# LPDDR4X_SDRAM.net
KiCad netlist of a schematic drawn in Altium Designer
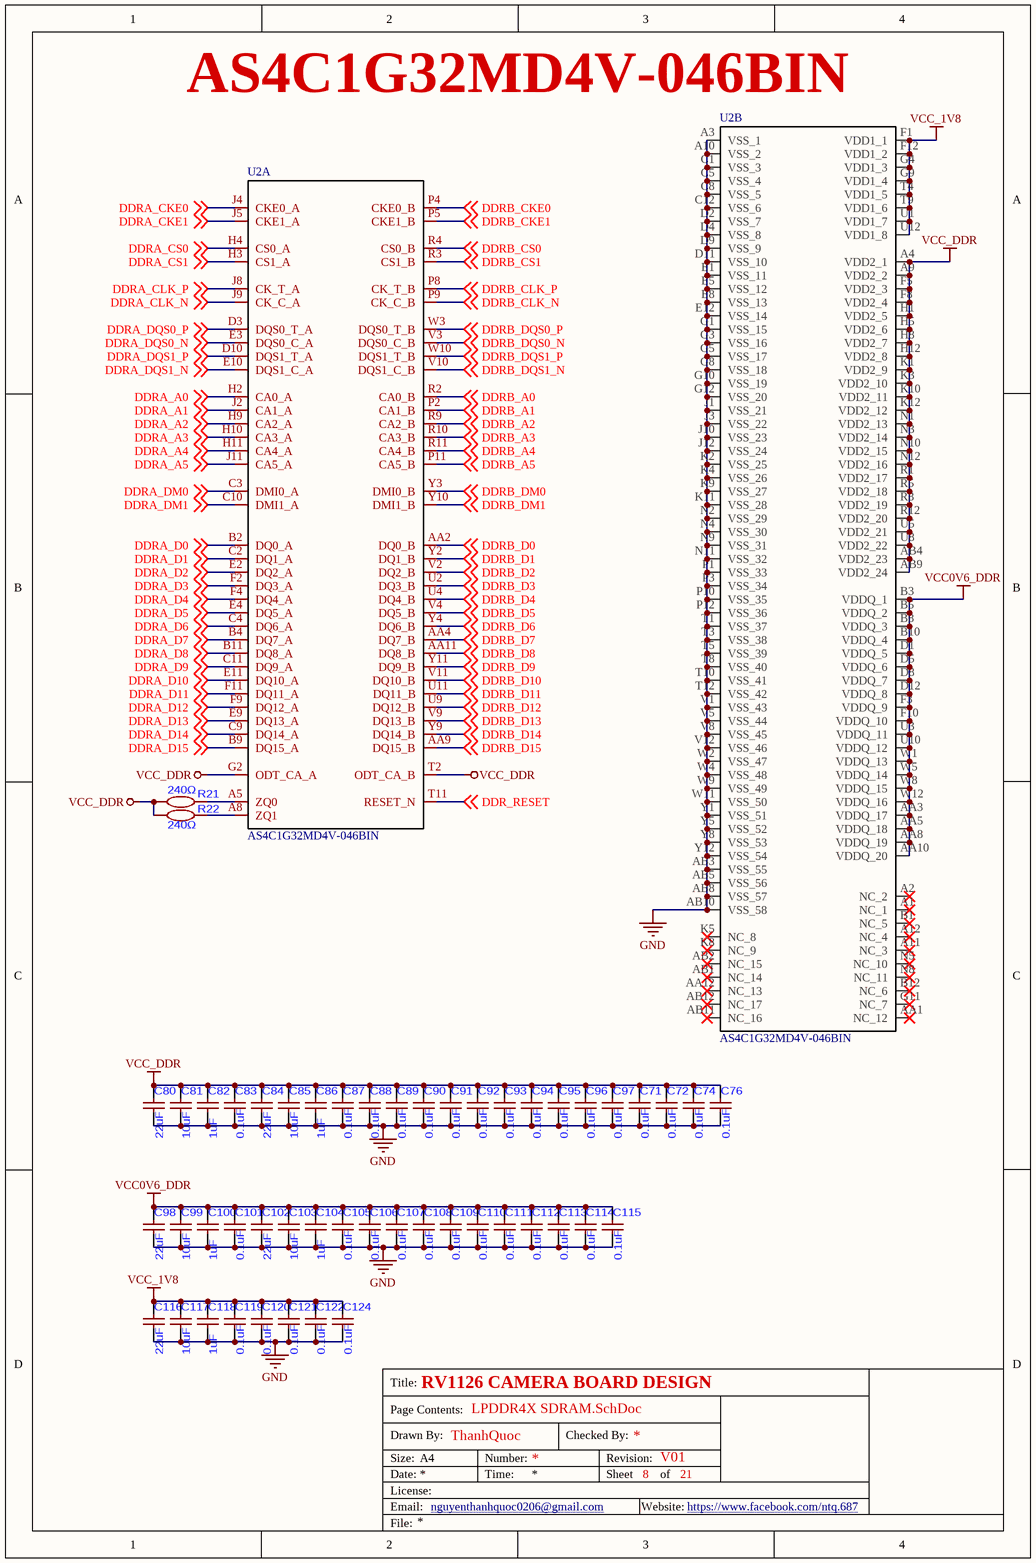
[diagram p0: LPDDR4X SDRAM.SchDoc]

(export (version "E")
  (design (tool "Eeschema 10.0.6"))
  (components
    (comp (ref "C71")
      (value "0.1uF")
      (footprint "C0201")
      (description "0.1uF ±10% 6.3V Ceramic Capacitor X5R 0201")
      (libsource (lib "Schlib1") (part "CAP_100nF-6.3V-10%-0201_1"))
    )
    (comp (ref "C72")
      (value "0.1uF")
      (footprint "C0201")
      (description "0.1uF ±10% 6.3V Ceramic Capacitor X5R 0201")
      (libsource (lib "Schlib1") (part "CAP_100nF-6.3V-10%-0201_1"))
    )
    (comp (ref "C74")
      (value "0.1uF")
      (footprint "C0201")
      (description "0.1uF ±10% 6.3V Ceramic Capacitor X5R 0201")
      (libsource (lib "Schlib1") (part "CAP_100nF-6.3V-10%-0201_1"))
    )
    (comp (ref "C76")
      (value "0.1uF")
      (footprint "C0201")
      (description "0.1uF ±10% 6.3V Ceramic Capacitor X5R 0201")
      (libsource (lib "Schlib1") (part "CAP_100nF-6.3V-10%-0201_1"))
    )
    (comp (ref "C80")
      (value "22uF")
      (footprint "C0402")
      (description "22uF X5R ±20% 6.3V 0402 Ceramic Capacitors RoHS")
      (libsource (lib "Schlib1") (part "CAP_22uF-6.3V-20%-0402"))
    )
    (comp (ref "C81")
      (value "10uF")
      (footprint "C0402")
      (description "10µF ±20% 10V Ceramic Capacitor X5R 0402 (1005 Metric)")
      (libsource (lib "Schlib1") (part "CAP_10uF-10V-20%-0402"))
    )
    (comp (ref "C82")
      (value "1uF")
      (footprint "C0201")
      (description "1uF ±10% 6.3V Ceramic Capacitor X5R 0201")
      (libsource (lib "Schlib1") (part "CAP_1uF-6.3V-10%-0201"))
    )
    (comp (ref "C83")
      (value "0.1uF")
      (footprint "C0201")
      (description "0.1uF ±10% 6.3V Ceramic Capacitor X5R 0201")
      (libsource (lib "Schlib1") (part "CAP_100nF-6.3V-10%-0201_1"))
    )
    (comp (ref "C84")
      (value "22uF")
      (footprint "C0402")
      (description "22uF X5R ±20% 6.3V 0402 Ceramic Capacitors RoHS")
      (libsource (lib "Schlib1") (part "CAP_22uF-6.3V-20%-0402"))
    )
    (comp (ref "C85")
      (value "10uF")
      (footprint "C0402")
      (description "10µF ±20% 10V Ceramic Capacitor X5R 0402 (1005 Metric)")
      (libsource (lib "Schlib1") (part "CAP_10uF-10V-20%-0402"))
    )
    (comp (ref "C86")
      (value "1uF")
      (footprint "C0201")
      (description "1uF ±10% 6.3V Ceramic Capacitor X5R 0201")
      (libsource (lib "Schlib1") (part "CAP_1uF-6.3V-10%-0201"))
    )
    (comp (ref "C87")
      (value "0.1uF")
      (footprint "C0201")
      (description "0.1uF ±10% 6.3V Ceramic Capacitor X5R 0201")
      (libsource (lib "Schlib1") (part "CAP_100nF-6.3V-10%-0201_1"))
    )
    (comp (ref "C88")
      (value "0.1uF")
      (footprint "C0201")
      (description "0.1uF ±10% 6.3V Ceramic Capacitor X5R 0201")
      (libsource (lib "Schlib1") (part "CAP_100nF-6.3V-10%-0201_1"))
    )
    (comp (ref "C89")
      (value "0.1uF")
      (footprint "C0201")
      (description "0.1uF ±10% 6.3V Ceramic Capacitor X5R 0201")
      (libsource (lib "Schlib1") (part "CAP_100nF-6.3V-10%-0201_1"))
    )
    (comp (ref "C90")
      (value "0.1uF")
      (footprint "C0201")
      (description "0.1uF ±10% 6.3V Ceramic Capacitor X5R 0201")
      (libsource (lib "Schlib1") (part "CAP_100nF-6.3V-10%-0201_1"))
    )
    (comp (ref "C91")
      (value "0.1uF")
      (footprint "C0201")
      (description "0.1uF ±10% 6.3V Ceramic Capacitor X5R 0201")
      (libsource (lib "Schlib1") (part "CAP_100nF-6.3V-10%-0201_1"))
    )
    (comp (ref "C92")
      (value "0.1uF")
      (footprint "C0201")
      (description "0.1uF ±10% 6.3V Ceramic Capacitor X5R 0201")
      (libsource (lib "Schlib1") (part "CAP_100nF-6.3V-10%-0201_1"))
    )
    (comp (ref "C93")
      (value "0.1uF")
      (footprint "C0201")
      (description "0.1uF ±10% 6.3V Ceramic Capacitor X5R 0201")
      (libsource (lib "Schlib1") (part "CAP_100nF-6.3V-10%-0201_1"))
    )
    (comp (ref "C94")
      (value "0.1uF")
      (footprint "C0201")
      (description "0.1uF ±10% 6.3V Ceramic Capacitor X5R 0201")
      (libsource (lib "Schlib1") (part "CAP_100nF-6.3V-10%-0201_1"))
    )
    (comp (ref "C95")
      (value "0.1uF")
      (footprint "C0201")
      (description "0.1uF ±10% 6.3V Ceramic Capacitor X5R 0201")
      (libsource (lib "Schlib1") (part "CAP_100nF-6.3V-10%-0201_1"))
    )
    (comp (ref "C96")
      (value "0.1uF")
      (footprint "C0201")
      (description "0.1uF ±10% 6.3V Ceramic Capacitor X5R 0201")
      (libsource (lib "Schlib1") (part "CAP_100nF-6.3V-10%-0201_1"))
    )
    (comp (ref "C97")
      (value "0.1uF")
      (footprint "C0201")
      (description "0.1uF ±10% 6.3V Ceramic Capacitor X5R 0201")
      (libsource (lib "Schlib1") (part "CAP_100nF-6.3V-10%-0201_1"))
    )
    (comp (ref "C98")
      (value "22uF")
      (footprint "C0402")
      (description "22uF X5R ±20% 6.3V 0402 Ceramic Capacitors RoHS")
      (libsource (lib "Schlib1") (part "CAP_22uF-6.3V-20%-0402"))
    )
    (comp (ref "C99")
      (value "10uF")
      (footprint "C0402")
      (description "10µF ±20% 10V Ceramic Capacitor X5R 0402 (1005 Metric)")
      (libsource (lib "Schlib1") (part "CAP_10uF-10V-20%-0402"))
    )
    (comp (ref "C100")
      (value "1uF")
      (footprint "C0201")
      (description "1uF ±10% 6.3V Ceramic Capacitor X5R 0201")
      (libsource (lib "Schlib1") (part "CAP_1uF-6.3V-10%-0201"))
    )
    (comp (ref "C101")
      (value "0.1uF")
      (footprint "C0201")
      (description "0.1uF ±10% 6.3V Ceramic Capacitor X5R 0201")
      (libsource (lib "Schlib1") (part "CAP_100nF-6.3V-10%-0201_1"))
    )
    (comp (ref "C102")
      (value "22uF")
      (footprint "C0402")
      (description "22uF X5R ±20% 6.3V 0402 Ceramic Capacitors RoHS")
      (libsource (lib "Schlib1") (part "CAP_22uF-6.3V-20%-0402"))
    )
    (comp (ref "C103")
      (value "10uF")
      (footprint "C0402")
      (description "10µF ±20% 10V Ceramic Capacitor X5R 0402 (1005 Metric)")
      (libsource (lib "Schlib1") (part "CAP_10uF-10V-20%-0402"))
    )
    (comp (ref "C104")
      (value "1uF")
      (footprint "C0201")
      (description "1uF ±10% 6.3V Ceramic Capacitor X5R 0201")
      (libsource (lib "Schlib1") (part "CAP_1uF-6.3V-10%-0201"))
    )
    (comp (ref "C105")
      (value "0.1uF")
      (footprint "C0201")
      (description "0.1uF ±10% 6.3V Ceramic Capacitor X5R 0201")
      (libsource (lib "Schlib1") (part "CAP_100nF-6.3V-10%-0201_1"))
    )
    (comp (ref "C106")
      (value "0.1uF")
      (footprint "C0201")
      (description "0.1uF ±10% 6.3V Ceramic Capacitor X5R 0201")
      (libsource (lib "Schlib1") (part "CAP_100nF-6.3V-10%-0201_1"))
    )
    (comp (ref "C107")
      (value "0.1uF")
      (footprint "C0201")
      (description "0.1uF ±10% 6.3V Ceramic Capacitor X5R 0201")
      (libsource (lib "Schlib1") (part "CAP_100nF-6.3V-10%-0201_1"))
    )
    (comp (ref "C108")
      (value "0.1uF")
      (footprint "C0201")
      (description "0.1uF ±10% 6.3V Ceramic Capacitor X5R 0201")
      (libsource (lib "Schlib1") (part "CAP_100nF-6.3V-10%-0201_1"))
    )
    (comp (ref "C109")
      (value "0.1uF")
      (footprint "C0201")
      (description "0.1uF ±10% 6.3V Ceramic Capacitor X5R 0201")
      (libsource (lib "Schlib1") (part "CAP_100nF-6.3V-10%-0201_1"))
    )
    (comp (ref "C110")
      (value "0.1uF")
      (footprint "C0201")
      (description "0.1uF ±10% 6.3V Ceramic Capacitor X5R 0201")
      (libsource (lib "Schlib1") (part "CAP_100nF-6.3V-10%-0201_1"))
    )
    (comp (ref "C111")
      (value "0.1uF")
      (footprint "C0201")
      (description "0.1uF ±10% 6.3V Ceramic Capacitor X5R 0201")
      (libsource (lib "Schlib1") (part "CAP_100nF-6.3V-10%-0201_1"))
    )
    (comp (ref "C112")
      (value "0.1uF")
      (footprint "C0201")
      (description "0.1uF ±10% 6.3V Ceramic Capacitor X5R 0201")
      (libsource (lib "Schlib1") (part "CAP_100nF-6.3V-10%-0201_1"))
    )
    (comp (ref "C113")
      (value "0.1uF")
      (footprint "C0201")
      (description "0.1uF ±10% 6.3V Ceramic Capacitor X5R 0201")
      (libsource (lib "Schlib1") (part "CAP_100nF-6.3V-10%-0201_1"))
    )
    (comp (ref "C114")
      (value "0.1uF")
      (footprint "C0201")
      (description "0.1uF ±10% 6.3V Ceramic Capacitor X5R 0201")
      (libsource (lib "Schlib1") (part "CAP_100nF-6.3V-10%-0201_1"))
    )
    (comp (ref "C115")
      (value "0.1uF")
      (footprint "C0201")
      (description "0.1uF ±10% 6.3V Ceramic Capacitor X5R 0201")
      (libsource (lib "Schlib1") (part "CAP_100nF-6.3V-10%-0201_1"))
    )
    (comp (ref "C116")
      (value "22uF")
      (footprint "C0402")
      (description "22uF X5R ±20% 6.3V 0402 Ceramic Capacitors RoHS")
      (libsource (lib "Schlib1") (part "CAP_22uF-6.3V-20%-0402"))
    )
    (comp (ref "C117")
      (value "10uF")
      (footprint "C0402")
      (description "10µF ±20% 10V Ceramic Capacitor X5R 0402 (1005 Metric)")
      (libsource (lib "Schlib1") (part "CAP_10uF-10V-20%-0402"))
    )
    (comp (ref "C118")
      (value "1uF")
      (footprint "C0201")
      (description "1uF ±10% 6.3V Ceramic Capacitor X5R 0201")
      (libsource (lib "Schlib1") (part "CAP_1uF-6.3V-10%-0201"))
    )
    (comp (ref "C119")
      (value "0.1uF")
      (footprint "C0201")
      (description "0.1uF ±10% 6.3V Ceramic Capacitor X5R 0201")
      (libsource (lib "Schlib1") (part "CAP_100nF-6.3V-10%-0201_1"))
    )
    (comp (ref "C120")
      (value "0.1uF")
      (footprint "C0201")
      (description "0.1uF ±10% 6.3V Ceramic Capacitor X5R 0201")
      (libsource (lib "Schlib1") (part "CAP_100nF-6.3V-10%-0201_1"))
    )
    (comp (ref "C121")
      (value "0.1uF")
      (footprint "C0201")
      (description "0.1uF ±10% 6.3V Ceramic Capacitor X5R 0201")
      (libsource (lib "Schlib1") (part "CAP_100nF-6.3V-10%-0201_1"))
    )
    (comp (ref "C122")
      (value "0.1uF")
      (footprint "C0201")
      (description "0.1uF ±10% 6.3V Ceramic Capacitor X5R 0201")
      (libsource (lib "Schlib1") (part "CAP_100nF-6.3V-10%-0201_1"))
    )
    (comp (ref "C124")
      (value "0.1uF")
      (footprint "C0201")
      (description "0.1uF ±10% 6.3V Ceramic Capacitor X5R 0201")
      (libsource (lib "Schlib1") (part "CAP_100nF-6.3V-10%-0201_1"))
    )
    (comp (ref "R21")
      (value "240Ω")
      (footprint "R0201")
      (description "RES 240Ω ±1% 50mW 0201")
      (libsource (lib "Schlib1") (part "RES_240-0.063W-1%-0201"))
    )
    (comp (ref "R22")
      (value "240Ω")
      (footprint "R0201")
      (description "RES 240Ω ±1% 50mW 0201")
      (libsource (lib "Schlib1") (part "RES_240-0.063W-1%-0201"))
    )
    (comp (ref "U2")
      (value "AS4C1G32MD4V-046BIN")
      (footprint "BGA200C65P12X22_1000X1500X100")
      (description "DRAM LPDDR4X, 32Gb, 1G X 32, 0.6v, 200ball TFBGA,2133MHZ,industrial Temp")
      (fields (field (name "MOUSER PART NUMBER") "913-AS4C1G32MD4046BI"))
      (libsource (lib "Schlib1") (part "AS4C1G32MD4V-046BIN"))
    )
  )
  (nets
    (net (code "1") (name "DDRA_A0") (class "Default")
      (node (ref "U2") (pin "H2") (pinfunction "CA0_A_H2") (pintype "passive"))
    )
    (net (code "2") (name "DDRA_A1") (class "Default")
      (node (ref "U2") (pin "J2") (pinfunction "CA1_A_J2") (pintype "passive"))
    )
    (net (code "3") (name "DDRA_A2") (class "Default")
      (node (ref "U2") (pin "H9") (pinfunction "CA2_A_H9") (pintype "passive"))
    )
    (net (code "4") (name "DDRA_A3") (class "Default")
      (node (ref "U2") (pin "H10") (pinfunction "CA3_A_H10") (pintype "passive"))
    )
    (net (code "5") (name "DDRA_A4") (class "Default")
      (node (ref "U2") (pin "H11") (pinfunction "CA4_A_H11") (pintype "passive"))
    )
    (net (code "6") (name "DDRA_A5") (class "Default")
      (node (ref "U2") (pin "J11") (pinfunction "CA5_A_J11") (pintype "passive"))
    )
    (net (code "7") (name "DDRA_CKE0") (class "Default")
      (node (ref "U2") (pin "J4") (pinfunction "CKE0_A_J4") (pintype "passive"))
    )
    (net (code "8") (name "DDRA_CKE1") (class "Default")
      (node (ref "U2") (pin "J5") (pinfunction "CKE1_A_J5") (pintype "passive"))
    )
    (net (code "9") (name "DDRA_CLK_N") (class "Default")
      (node (ref "U2") (pin "J9") (pinfunction "CK_C_A_J9") (pintype "passive"))
    )
    (net (code "10") (name "DDRA_CLK_P") (class "Default")
      (node (ref "U2") (pin "J8") (pinfunction "CK_T_A_J8") (pintype "passive"))
    )
    (net (code "11") (name "DDRA_CS0") (class "Default")
      (node (ref "U2") (pin "H4") (pinfunction "CS0_A_H4") (pintype "passive"))
    )
    (net (code "12") (name "DDRA_CS1") (class "Default")
      (node (ref "U2") (pin "H3") (pinfunction "CS1_A_H3") (pintype "passive"))
    )
    (net (code "13") (name "DDRA_D0") (class "Default")
      (node (ref "U2") (pin "B2") (pinfunction "DQ0_A_B2") (pintype "passive"))
    )
    (net (code "14") (name "DDRA_D1") (class "Default")
      (node (ref "U2") (pin "C2") (pinfunction "DQ1_A_C2") (pintype "passive"))
    )
    (net (code "15") (name "DDRA_D2") (class "Default")
      (node (ref "U2") (pin "E2") (pinfunction "DQ2_A_E2") (pintype "passive"))
    )
    (net (code "16") (name "DDRA_D3") (class "Default")
      (node (ref "U2") (pin "F2") (pinfunction "DQ3_A_F2") (pintype "passive"))
    )
    (net (code "17") (name "DDRA_D4") (class "Default")
      (node (ref "U2") (pin "F4") (pinfunction "DQ4_A_F4") (pintype "passive"))
    )
    (net (code "18") (name "DDRA_D5") (class "Default")
      (node (ref "U2") (pin "E4") (pinfunction "DQ5_A_E4") (pintype "passive"))
    )
    (net (code "19") (name "DDRA_D6") (class "Default")
      (node (ref "U2") (pin "C4") (pinfunction "DQ6_A_C4") (pintype "passive"))
    )
    (net (code "20") (name "DDRA_D7") (class "Default")
      (node (ref "U2") (pin "B4") (pinfunction "DQ7_A_B4") (pintype "passive"))
    )
    (net (code "21") (name "DDRA_D8") (class "Default")
      (node (ref "U2") (pin "B11") (pinfunction "DQ8_A_B11") (pintype "passive"))
    )
    (net (code "22") (name "DDRA_D9") (class "Default")
      (node (ref "U2") (pin "C11") (pinfunction "DQ9_A_C11") (pintype "passive"))
    )
    (net (code "23") (name "DDRA_D10") (class "Default")
      (node (ref "U2") (pin "E11") (pinfunction "DQ10_A_E11") (pintype "passive"))
    )
    (net (code "24") (name "DDRA_D11") (class "Default")
      (node (ref "U2") (pin "F11") (pinfunction "DQ11_A_F11") (pintype "passive"))
    )
    (net (code "25") (name "DDRA_D12") (class "Default")
      (node (ref "U2") (pin "F9") (pinfunction "DQ12_A_F9") (pintype "passive"))
    )
    (net (code "26") (name "DDRA_D13") (class "Default")
      (node (ref "U2") (pin "E9") (pinfunction "DQ13_A_E9") (pintype "passive"))
    )
    (net (code "27") (name "DDRA_D14") (class "Default")
      (node (ref "U2") (pin "C9") (pinfunction "DQ14_A_C9") (pintype "passive"))
    )
    (net (code "28") (name "DDRA_D15") (class "Default")
      (node (ref "U2") (pin "B9") (pinfunction "DQ15_A_B9") (pintype "passive"))
    )
    (net (code "29") (name "DDRA_DM0") (class "Default")
      (node (ref "U2") (pin "C3") (pinfunction "DMI0_A_C3") (pintype "passive"))
    )
    (net (code "30") (name "DDRA_DM1") (class "Default")
      (node (ref "U2") (pin "C10") (pinfunction "DMI1_A_C10") (pintype "passive"))
    )
    (net (code "31") (name "DDRA_DQS0_N") (class "Default")
      (node (ref "U2") (pin "E3") (pinfunction "DQS0_C_A_E3") (pintype "passive"))
    )
    (net (code "32") (name "DDRA_DQS0_P") (class "Default")
      (node (ref "U2") (pin "D3") (pinfunction "DQS0_T_A_D3") (pintype "passive"))
    )
    (net (code "33") (name "DDRA_DQS1_N") (class "Default")
      (node (ref "U2") (pin "E10") (pinfunction "DQS1_C_A_E10") (pintype "passive"))
    )
    (net (code "34") (name "DDRA_DQS1_P") (class "Default")
      (node (ref "U2") (pin "D10") (pinfunction "DQS1_T_A_D10") (pintype "passive"))
    )
    (net (code "35") (name "DDRB_A0") (class "Default")
      (node (ref "U2") (pin "R2") (pinfunction "CA0_B_R2") (pintype "passive"))
    )
    (net (code "36") (name "DDRB_A1") (class "Default")
      (node (ref "U2") (pin "P2") (pinfunction "CA1_B_P2") (pintype "passive"))
    )
    (net (code "37") (name "DDRB_A2") (class "Default")
      (node (ref "U2") (pin "R9") (pinfunction "CA2_B_R9") (pintype "passive"))
    )
    (net (code "38") (name "DDRB_A3") (class "Default")
      (node (ref "U2") (pin "R10") (pinfunction "CA3_B_R10") (pintype "passive"))
    )
    (net (code "39") (name "DDRB_A4") (class "Default")
      (node (ref "U2") (pin "R11") (pinfunction "CA4_B_R11") (pintype "passive"))
    )
    (net (code "40") (name "DDRB_A5") (class "Default")
      (node (ref "U2") (pin "P11") (pinfunction "CA5_B_P11") (pintype "passive"))
    )
    (net (code "41") (name "DDRB_CKE0") (class "Default")
      (node (ref "U2") (pin "P4") (pinfunction "CKE0_B_P4") (pintype "passive"))
    )
    (net (code "42") (name "DDRB_CKE1") (class "Default")
      (node (ref "U2") (pin "P5") (pinfunction "CKE1_B_P5") (pintype "passive"))
    )
    (net (code "43") (name "DDRB_CLK_N") (class "Default")
      (node (ref "U2") (pin "P9") (pinfunction "CK_C_B_P9") (pintype "passive"))
    )
    (net (code "44") (name "DDRB_CLK_P") (class "Default")
      (node (ref "U2") (pin "P8") (pinfunction "CK_T_B_P8") (pintype "passive"))
    )
    (net (code "45") (name "DDRB_CS0") (class "Default")
      (node (ref "U2") (pin "R4") (pinfunction "CS0_B_R4") (pintype "passive"))
    )
    (net (code "46") (name "DDRB_CS1") (class "Default")
      (node (ref "U2") (pin "R3") (pinfunction "CS1_B_R3") (pintype "passive"))
    )
    (net (code "47") (name "DDRB_D0") (class "Default")
      (node (ref "U2") (pin "AA2") (pinfunction "DQ0_B_AA2") (pintype "passive"))
    )
    (net (code "48") (name "DDRB_D1") (class "Default")
      (node (ref "U2") (pin "Y2") (pinfunction "DQ1_B_Y2") (pintype "passive"))
    )
    (net (code "49") (name "DDRB_D2") (class "Default")
      (node (ref "U2") (pin "V2") (pinfunction "DQ2_B_V2") (pintype "passive"))
    )
    (net (code "50") (name "DDRB_D3") (class "Default")
      (node (ref "U2") (pin "U2") (pinfunction "DQ3_B_U2") (pintype "passive"))
    )
    (net (code "51") (name "DDRB_D4") (class "Default")
      (node (ref "U2") (pin "U4") (pinfunction "DQ4_B_U4") (pintype "passive"))
    )
    (net (code "52") (name "DDRB_D5") (class "Default")
      (node (ref "U2") (pin "V4") (pinfunction "DQ5_B_V4") (pintype "passive"))
    )
    (net (code "53") (name "DDRB_D6") (class "Default")
      (node (ref "U2") (pin "Y4") (pinfunction "DQ6_B_Y4") (pintype "passive"))
    )
    (net (code "54") (name "DDRB_D7") (class "Default")
      (node (ref "U2") (pin "AA4") (pinfunction "DQ7_B_AA4") (pintype "passive"))
    )
    (net (code "55") (name "DDRB_D8") (class "Default")
      (node (ref "U2") (pin "AA11") (pinfunction "DQ8_B_AA11") (pintype "passive"))
    )
    (net (code "56") (name "DDRB_D9") (class "Default")
      (node (ref "U2") (pin "Y11") (pinfunction "DQ9_B_Y11") (pintype "passive"))
    )
    (net (code "57") (name "DDRB_D10") (class "Default")
      (node (ref "U2") (pin "V11") (pinfunction "DQ10_B_V11") (pintype "passive"))
    )
    (net (code "58") (name "DDRB_D11") (class "Default")
      (node (ref "U2") (pin "U11") (pinfunction "DQ11_B_U11") (pintype "passive"))
    )
    (net (code "59") (name "DDRB_D12") (class "Default")
      (node (ref "U2") (pin "U9") (pinfunction "DQ12_B_U9") (pintype "passive"))
    )
    (net (code "60") (name "DDRB_D13") (class "Default")
      (node (ref "U2") (pin "V9") (pinfunction "DQ13_B_V9") (pintype "passive"))
    )
    (net (code "61") (name "DDRB_D14") (class "Default")
      (node (ref "U2") (pin "Y9") (pinfunction "DQ14_B_Y9") (pintype "passive"))
    )
    (net (code "62") (name "DDRB_D15") (class "Default")
      (node (ref "U2") (pin "AA9") (pinfunction "DQ15_B_AA9") (pintype "passive"))
    )
    (net (code "63") (name "DDRB_DM0") (class "Default")
      (node (ref "U2") (pin "Y3") (pinfunction "DMI0_B_Y3") (pintype "passive"))
    )
    (net (code "64") (name "DDRB_DM1") (class "Default")
      (node (ref "U2") (pin "Y10") (pinfunction "DMI1_B_Y10") (pintype "passive"))
    )
    (net (code "65") (name "DDRB_DQS0_N") (class "Default")
      (node (ref "U2") (pin "V3") (pinfunction "DQS0_C_B_V3") (pintype "passive"))
    )
    (net (code "66") (name "DDRB_DQS0_P") (class "Default")
      (node (ref "U2") (pin "W3") (pinfunction "DQS0_T_B_W3") (pintype "passive"))
    )
    (net (code "67") (name "DDRB_DQS1_N") (class "Default")
      (node (ref "U2") (pin "V10") (pinfunction "DQS1_C_B_V10") (pintype "passive"))
    )
    (net (code "68") (name "DDRB_DQS1_P") (class "Default")
      (node (ref "U2") (pin "W10") (pinfunction "DQS1_T_B_W10") (pintype "passive"))
    )
    (net (code "69") (name "DDR_RESET") (class "Default")
      (node (ref "U2") (pin "T11") (pinfunction "RESET_N_T11") (pintype "passive"))
    )
    (net (code "70") (name "GND") (class "Default")
      (node (ref "C100") (pin "1") (pinfunction "1_1") (pintype "passive"))
      (node (ref "C101") (pin "1") (pinfunction "1_1") (pintype "passive"))
      (node (ref "C102") (pin "1") (pinfunction "1_1") (pintype "passive"))
      (node (ref "C103") (pin "1") (pinfunction "1_1") (pintype "passive"))
      (node (ref "C104") (pin "1") (pinfunction "1_1") (pintype "passive"))
      (node (ref "C105") (pin "1") (pinfunction "1_1") (pintype "passive"))
      (node (ref "C106") (pin "1") (pinfunction "1_1") (pintype "passive"))
      (node (ref "C107") (pin "1") (pinfunction "1_1") (pintype "passive"))
      (node (ref "C108") (pin "1") (pinfunction "1_1") (pintype "passive"))
      (node (ref "C109") (pin "1") (pinfunction "1_1") (pintype "passive"))
      (node (ref "C110") (pin "1") (pinfunction "1_1") (pintype "passive"))
      (node (ref "C111") (pin "1") (pinfunction "1_1") (pintype "passive"))
      (node (ref "C112") (pin "1") (pinfunction "1_1") (pintype "passive"))
      (node (ref "C113") (pin "1") (pinfunction "1_1") (pintype "passive"))
      (node (ref "C114") (pin "1") (pinfunction "1_1") (pintype "passive"))
      (node (ref "C115") (pin "1") (pinfunction "1_1") (pintype "passive"))
      (node (ref "C116") (pin "1") (pinfunction "1_1") (pintype "passive"))
      (node (ref "C117") (pin "1") (pinfunction "1_1") (pintype "passive"))
      (node (ref "C118") (pin "1") (pinfunction "1_1") (pintype "passive"))
      (node (ref "C119") (pin "1") (pinfunction "1_1") (pintype "passive"))
      (node (ref "C120") (pin "1") (pinfunction "1_1") (pintype "passive"))
      (node (ref "C121") (pin "1") (pinfunction "1_1") (pintype "passive"))
      (node (ref "C122") (pin "1") (pinfunction "1_1") (pintype "passive"))
      (node (ref "C124") (pin "1") (pinfunction "1_1") (pintype "passive"))
      (node (ref "C71") (pin "1") (pinfunction "1_1") (pintype "passive"))
      (node (ref "C72") (pin "1") (pinfunction "1_1") (pintype "passive"))
      (node (ref "C74") (pin "1") (pinfunction "1_1") (pintype "passive"))
      (node (ref "C76") (pin "1") (pinfunction "1_1") (pintype "passive"))
      (node (ref "C80") (pin "1") (pinfunction "1_1") (pintype "passive"))
      (node (ref "C81") (pin "1") (pinfunction "1_1") (pintype "passive"))
      (node (ref "C82") (pin "1") (pinfunction "1_1") (pintype "passive"))
      (node (ref "C83") (pin "1") (pinfunction "1_1") (pintype "passive"))
      (node (ref "C84") (pin "1") (pinfunction "1_1") (pintype "passive"))
      (node (ref "C85") (pin "1") (pinfunction "1_1") (pintype "passive"))
      (node (ref "C86") (pin "1") (pinfunction "1_1") (pintype "passive"))
      (node (ref "C87") (pin "1") (pinfunction "1_1") (pintype "passive"))
      (node (ref "C88") (pin "1") (pinfunction "1_1") (pintype "passive"))
      (node (ref "C89") (pin "1") (pinfunction "1_1") (pintype "passive"))
      (node (ref "C90") (pin "1") (pinfunction "1_1") (pintype "passive"))
      (node (ref "C91") (pin "1") (pinfunction "1_1") (pintype "passive"))
      (node (ref "C92") (pin "1") (pinfunction "1_1") (pintype "passive"))
      (node (ref "C93") (pin "1") (pinfunction "1_1") (pintype "passive"))
      (node (ref "C94") (pin "1") (pinfunction "1_1") (pintype "passive"))
      (node (ref "C95") (pin "1") (pinfunction "1_1") (pintype "passive"))
      (node (ref "C96") (pin "1") (pinfunction "1_1") (pintype "passive"))
      (node (ref "C97") (pin "1") (pinfunction "1_1") (pintype "passive"))
      (node (ref "C98") (pin "1") (pinfunction "1_1") (pintype "passive"))
      (node (ref "C99") (pin "1") (pinfunction "1_1") (pintype "passive"))
      (node (ref "U2") (pin "A10") (pinfunction "VSS_2_A10") (pintype "passive"))
      (node (ref "U2") (pin "A3") (pinfunction "VSS_1_A3") (pintype "passive"))
      (node (ref "U2") (pin "AB10") (pinfunction "VSS_58_AB10") (pintype "passive"))
      (node (ref "U2") (pin "AB3") (pinfunction "VSS_55_AB3") (pintype "passive"))
      (node (ref "U2") (pin "AB5") (pinfunction "VSS_56_AB5") (pintype "passive"))
      (node (ref "U2") (pin "AB8") (pinfunction "VSS_57_AB8") (pintype "passive"))
      (node (ref "U2") (pin "C1") (pinfunction "VSS_3_C1") (pintype "passive"))
      (node (ref "U2") (pin "C12") (pinfunction "VSS_6_C12") (pintype "passive"))
      (node (ref "U2") (pin "C5") (pinfunction "VSS_4_C5") (pintype "passive"))
      (node (ref "U2") (pin "C8") (pinfunction "VSS_5_C8") (pintype "passive"))
      (node (ref "U2") (pin "D11") (pinfunction "VSS_10_D11") (pintype "passive"))
      (node (ref "U2") (pin "D2") (pinfunction "VSS_7_D2") (pintype "passive"))
      (node (ref "U2") (pin "D4") (pinfunction "VSS_8_D4") (pintype "passive"))
      (node (ref "U2") (pin "D9") (pinfunction "VSS_9_D9") (pintype "passive"))
      (node (ref "U2") (pin "E1") (pinfunction "VSS_11_E1") (pintype "passive"))
      (node (ref "U2") (pin "E12") (pinfunction "VSS_14_E12") (pintype "passive"))
      (node (ref "U2") (pin "E5") (pinfunction "VSS_12_E5") (pintype "passive"))
      (node (ref "U2") (pin "E8") (pinfunction "VSS_13_E8") (pintype "passive"))
      (node (ref "U2") (pin "G1") (pinfunction "VSS_15_G1") (pintype "passive"))
      (node (ref "U2") (pin "G10") (pinfunction "VSS_19_G10") (pintype "passive"))
      (node (ref "U2") (pin "G12") (pinfunction "VSS_20_G12") (pintype "passive"))
      (node (ref "U2") (pin "G3") (pinfunction "VSS_16_G3") (pintype "passive"))
      (node (ref "U2") (pin "G5") (pinfunction "VSS_17_G5") (pintype "passive"))
      (node (ref "U2") (pin "G8") (pinfunction "VSS_18_G8") (pintype "passive"))
      (node (ref "U2") (pin "J1") (pinfunction "VSS_21_J1") (pintype "passive"))
      (node (ref "U2") (pin "J10") (pinfunction "VSS_23_J10") (pintype "passive"))
      (node (ref "U2") (pin "J12") (pinfunction "VSS_24_J12") (pintype "passive"))
      (node (ref "U2") (pin "J3") (pinfunction "VSS_22_J3") (pintype "passive"))
      (node (ref "U2") (pin "K11") (pinfunction "VSS_28_K11") (pintype "passive"))
      (node (ref "U2") (pin "K2") (pinfunction "VSS_25_K2") (pintype "passive"))
      (node (ref "U2") (pin "K4") (pinfunction "VSS_26_K4") (pintype "passive"))
      (node (ref "U2") (pin "K9") (pinfunction "VSS_27_K9") (pintype "passive"))
      (node (ref "U2") (pin "N11") (pinfunction "VSS_32_N11") (pintype "passive"))
      (node (ref "U2") (pin "N2") (pinfunction "VSS_29_N2") (pintype "passive"))
      (node (ref "U2") (pin "N4") (pinfunction "VSS_30_N4") (pintype "passive"))
      (node (ref "U2") (pin "N9") (pinfunction "VSS_31_N9") (pintype "passive"))
      (node (ref "U2") (pin "P1") (pinfunction "VSS_33_P1") (pintype "passive"))
      (node (ref "U2") (pin "P10") (pinfunction "VSS_35_P10") (pintype "passive"))
      (node (ref "U2") (pin "P12") (pinfunction "VSS_36_P12") (pintype "passive"))
      (node (ref "U2") (pin "P3") (pinfunction "VSS_34_P3") (pintype "passive"))
      (node (ref "U2") (pin "T1") (pinfunction "VSS_37_T1") (pintype "passive"))
      (node (ref "U2") (pin "T10") (pinfunction "VSS_41_T10") (pintype "passive"))
      (node (ref "U2") (pin "T12") (pinfunction "VSS_42_T12") (pintype "passive"))
      (node (ref "U2") (pin "T3") (pinfunction "VSS_38_T3") (pintype "passive"))
      (node (ref "U2") (pin "T5") (pinfunction "VSS_39_T5") (pintype "passive"))
      (node (ref "U2") (pin "T8") (pinfunction "VSS_40_T8") (pintype "passive"))
      (node (ref "U2") (pin "V1") (pinfunction "VSS_43_V1") (pintype "passive"))
      (node (ref "U2") (pin "V12") (pinfunction "VSS_46_V12") (pintype "passive"))
      (node (ref "U2") (pin "V5") (pinfunction "VSS_44_V5") (pintype "passive"))
      (node (ref "U2") (pin "V8") (pinfunction "VSS_45_V8") (pintype "passive"))
      (node (ref "U2") (pin "W11") (pinfunction "VSS_50_W11") (pintype "passive"))
      (node (ref "U2") (pin "W2") (pinfunction "VSS_47_W2") (pintype "passive"))
      (node (ref "U2") (pin "W4") (pinfunction "VSS_48_W4") (pintype "passive"))
      (node (ref "U2") (pin "W9") (pinfunction "VSS_49_W9") (pintype "passive"))
      (node (ref "U2") (pin "Y1") (pinfunction "VSS_51_Y1") (pintype "passive"))
      (node (ref "U2") (pin "Y12") (pinfunction "VSS_54_Y12") (pintype "passive"))
      (node (ref "U2") (pin "Y5") (pinfunction "VSS_52_Y5") (pintype "passive"))
      (node (ref "U2") (pin "Y8") (pinfunction "VSS_53_Y8") (pintype "passive"))
    )
    (net (code "71") (name "Net-(U2A-ZQ0)") (class "Default")
      (node (ref "R21") (pin "2") (pinfunction "2_2") (pintype "passive"))
      (node (ref "U2") (pin "A5") (pinfunction "ZQ0_A5") (pintype "passive"))
    )
    (net (code "72") (name "Net-(U2A-ZQ1)") (class "Default")
      (node (ref "R22") (pin "2") (pinfunction "2_2") (pintype "passive"))
      (node (ref "U2") (pin "A8") (pinfunction "ZQ1_A8") (pintype "passive"))
    )
    (net (code "73") (name "VCC0V6_DDR") (class "Default")
      (node (ref "C100") (pin "2") (pinfunction "2_2") (pintype "passive"))
      (node (ref "C101") (pin "2") (pinfunction "2_2") (pintype "passive"))
      (node (ref "C102") (pin "2") (pinfunction "2_2") (pintype "passive"))
      (node (ref "C103") (pin "2") (pinfunction "2_2") (pintype "passive"))
      (node (ref "C104") (pin "2") (pinfunction "2_2") (pintype "passive"))
      (node (ref "C105") (pin "2") (pinfunction "2_2") (pintype "passive"))
      (node (ref "C106") (pin "2") (pinfunction "2_2") (pintype "passive"))
      (node (ref "C107") (pin "2") (pinfunction "2_2") (pintype "passive"))
      (node (ref "C108") (pin "2") (pinfunction "2_2") (pintype "passive"))
      (node (ref "C109") (pin "2") (pinfunction "2_2") (pintype "passive"))
      (node (ref "C110") (pin "2") (pinfunction "2_2") (pintype "passive"))
      (node (ref "C111") (pin "2") (pinfunction "2_2") (pintype "passive"))
      (node (ref "C112") (pin "2") (pinfunction "2_2") (pintype "passive"))
      (node (ref "C113") (pin "2") (pinfunction "2_2") (pintype "passive"))
      (node (ref "C114") (pin "2") (pinfunction "2_2") (pintype "passive"))
      (node (ref "C115") (pin "2") (pinfunction "2_2") (pintype "passive"))
      (node (ref "C98") (pin "2") (pinfunction "2_2") (pintype "passive"))
      (node (ref "C99") (pin "2") (pinfunction "2_2") (pintype "passive"))
      (node (ref "U2") (pin "AA10") (pinfunction "VDDQ_20_AA10") (pintype "passive"))
      (node (ref "U2") (pin "AA3") (pinfunction "VDDQ_17_AA3") (pintype "passive"))
      (node (ref "U2") (pin "AA5") (pinfunction "VDDQ_18_AA5") (pintype "passive"))
      (node (ref "U2") (pin "AA8") (pinfunction "VDDQ_19_AA8") (pintype "passive"))
      (node (ref "U2") (pin "B10") (pinfunction "VDDQ_4_B10") (pintype "passive"))
      (node (ref "U2") (pin "B3") (pinfunction "VDDQ_1_B3") (pintype "passive"))
      (node (ref "U2") (pin "B5") (pinfunction "VDDQ_2_B5") (pintype "passive"))
      (node (ref "U2") (pin "B8") (pinfunction "VDDQ_3_B8") (pintype "passive"))
      (node (ref "U2") (pin "D1") (pinfunction "VDDQ_5_D1") (pintype "passive"))
      (node (ref "U2") (pin "D12") (pinfunction "VDDQ_8_D12") (pintype "passive"))
      (node (ref "U2") (pin "D5") (pinfunction "VDDQ_6_D5") (pintype "passive"))
      (node (ref "U2") (pin "D8") (pinfunction "VDDQ_7_D8") (pintype "passive"))
      (node (ref "U2") (pin "F10") (pinfunction "VDDQ_10_F10") (pintype "passive"))
      (node (ref "U2") (pin "F3") (pinfunction "VDDQ_9_F3") (pintype "passive"))
      (node (ref "U2") (pin "U10") (pinfunction "VDDQ_12_U10") (pintype "passive"))
      (node (ref "U2") (pin "U3") (pinfunction "VDDQ_11_U3") (pintype "passive"))
      (node (ref "U2") (pin "W1") (pinfunction "VDDQ_13_W1") (pintype "passive"))
      (node (ref "U2") (pin "W12") (pinfunction "VDDQ_16_W12") (pintype "passive"))
      (node (ref "U2") (pin "W5") (pinfunction "VDDQ_14_W5") (pintype "passive"))
      (node (ref "U2") (pin "W8") (pinfunction "VDDQ_15_W8") (pintype "passive"))
    )
    (net (code "74") (name "VCC_1V8") (class "Default")
      (node (ref "C116") (pin "2") (pinfunction "2_2") (pintype "passive"))
      (node (ref "C117") (pin "2") (pinfunction "2_2") (pintype "passive"))
      (node (ref "C118") (pin "2") (pinfunction "2_2") (pintype "passive"))
      (node (ref "C119") (pin "2") (pinfunction "2_2") (pintype "passive"))
      (node (ref "C120") (pin "2") (pinfunction "2_2") (pintype "passive"))
      (node (ref "C121") (pin "2") (pinfunction "2_2") (pintype "passive"))
      (node (ref "C122") (pin "2") (pinfunction "2_2") (pintype "passive"))
      (node (ref "C124") (pin "2") (pinfunction "2_2") (pintype "passive"))
      (node (ref "U2") (pin "F1") (pinfunction "VDD1_1_F1") (pintype "passive"))
      (node (ref "U2") (pin "F12") (pinfunction "VDD1_2_F12") (pintype "passive"))
      (node (ref "U2") (pin "G4") (pinfunction "VDD1_3_G4") (pintype "passive"))
      (node (ref "U2") (pin "G9") (pinfunction "VDD1_4_G9") (pintype "passive"))
      (node (ref "U2") (pin "T4") (pinfunction "VDD1_5_T4") (pintype "passive"))
      (node (ref "U2") (pin "T9") (pinfunction "VDD1_6_T9") (pintype "passive"))
      (node (ref "U2") (pin "U1") (pinfunction "VDD1_7_U1") (pintype "passive"))
      (node (ref "U2") (pin "U12") (pinfunction "VDD1_8_U12") (pintype "passive"))
    )
    (net (code "75") (name "VCC_DDR") (class "Default")
      (node (ref "C71") (pin "2") (pinfunction "2_2") (pintype "passive"))
      (node (ref "C72") (pin "2") (pinfunction "2_2") (pintype "passive"))
      (node (ref "C74") (pin "2") (pinfunction "2_2") (pintype "passive"))
      (node (ref "C76") (pin "2") (pinfunction "2_2") (pintype "passive"))
      (node (ref "C80") (pin "2") (pinfunction "2_2") (pintype "passive"))
      (node (ref "C81") (pin "2") (pinfunction "2_2") (pintype "passive"))
      (node (ref "C82") (pin "2") (pinfunction "2_2") (pintype "passive"))
      (node (ref "C83") (pin "2") (pinfunction "2_2") (pintype "passive"))
      (node (ref "C84") (pin "2") (pinfunction "2_2") (pintype "passive"))
      (node (ref "C85") (pin "2") (pinfunction "2_2") (pintype "passive"))
      (node (ref "C86") (pin "2") (pinfunction "2_2") (pintype "passive"))
      (node (ref "C87") (pin "2") (pinfunction "2_2") (pintype "passive"))
      (node (ref "C88") (pin "2") (pinfunction "2_2") (pintype "passive"))
      (node (ref "C89") (pin "2") (pinfunction "2_2") (pintype "passive"))
      (node (ref "C90") (pin "2") (pinfunction "2_2") (pintype "passive"))
      (node (ref "C91") (pin "2") (pinfunction "2_2") (pintype "passive"))
      (node (ref "C92") (pin "2") (pinfunction "2_2") (pintype "passive"))
      (node (ref "C93") (pin "2") (pinfunction "2_2") (pintype "passive"))
      (node (ref "C94") (pin "2") (pinfunction "2_2") (pintype "passive"))
      (node (ref "C95") (pin "2") (pinfunction "2_2") (pintype "passive"))
      (node (ref "C96") (pin "2") (pinfunction "2_2") (pintype "passive"))
      (node (ref "C97") (pin "2") (pinfunction "2_2") (pintype "passive"))
      (node (ref "R21") (pin "1") (pinfunction "1_1") (pintype "passive"))
      (node (ref "R22") (pin "1") (pinfunction "1_1") (pintype "passive"))
      (node (ref "U2") (pin "A4") (pinfunction "VDD2_1_A4") (pintype "passive"))
      (node (ref "U2") (pin "A9") (pinfunction "VDD2_2_A9") (pintype "passive"))
      (node (ref "U2") (pin "AB4") (pinfunction "VDD2_23_AB4") (pintype "passive"))
      (node (ref "U2") (pin "AB9") (pinfunction "VDD2_24_AB9") (pintype "passive"))
      (node (ref "U2") (pin "F5") (pinfunction "VDD2_3_F5") (pintype "passive"))
      (node (ref "U2") (pin "F8") (pinfunction "VDD2_4_F8") (pintype "passive"))
      (node (ref "U2") (pin "G2") (pinfunction "ODT_CA_A_G2") (pintype "passive"))
      (node (ref "U2") (pin "H1") (pinfunction "VDD2_5_H1") (pintype "passive"))
      (node (ref "U2") (pin "H12") (pinfunction "VDD2_8_H12") (pintype "passive"))
      (node (ref "U2") (pin "H5") (pinfunction "VDD2_6_H5") (pintype "passive"))
      (node (ref "U2") (pin "H8") (pinfunction "VDD2_7_H8") (pintype "passive"))
      (node (ref "U2") (pin "K1") (pinfunction "VDD2_9_K1") (pintype "passive"))
      (node (ref "U2") (pin "K10") (pinfunction "VDD2_11_K10") (pintype "passive"))
      (node (ref "U2") (pin "K12") (pinfunction "VDD2_12_K12") (pintype "passive"))
      (node (ref "U2") (pin "K3") (pinfunction "VDD2_10_K3") (pintype "passive"))
      (node (ref "U2") (pin "N1") (pinfunction "VDD2_13_N1") (pintype "passive"))
      (node (ref "U2") (pin "N10") (pinfunction "VDD2_15_N10") (pintype "passive"))
      (node (ref "U2") (pin "N12") (pinfunction "VDD2_16_N12") (pintype "passive"))
      (node (ref "U2") (pin "N3") (pinfunction "VDD2_14_N3") (pintype "passive"))
      (node (ref "U2") (pin "R1") (pinfunction "VDD2_17_R1") (pintype "passive"))
      (node (ref "U2") (pin "R12") (pinfunction "VDD2_20_R12") (pintype "passive"))
      (node (ref "U2") (pin "R5") (pinfunction "VDD2_18_R5") (pintype "passive"))
      (node (ref "U2") (pin "R8") (pinfunction "VDD2_19_R8") (pintype "passive"))
      (node (ref "U2") (pin "T2") (pinfunction "ODT_CA_B_T2") (pintype "passive"))
      (node (ref "U2") (pin "U5") (pinfunction "VDD2_21_U5") (pintype "passive"))
      (node (ref "U2") (pin "U8") (pinfunction "VDD2_22_U8") (pintype "passive"))
    )
    (net (code "76") (name "unconnected-(U2B-NC_1-PadA1)") (class "Default")
      (node (ref "U2") (pin "A1") (pinfunction "NC_1_A1") (pintype "passive+no_connect"))
    )
    (net (code "77") (name "unconnected-(U2B-NC_2-PadA2)") (class "Default")
      (node (ref "U2") (pin "A2") (pinfunction "NC_2_A2") (pintype "passive+no_connect"))
    )
    (net (code "78") (name "unconnected-(U2B-NC_3-PadA11)") (class "Default")
      (node (ref "U2") (pin "A11") (pinfunction "NC_3_A11") (pintype "passive+no_connect"))
    )
    (net (code "79") (name "unconnected-(U2B-NC_4-PadA12)") (class "Default")
      (node (ref "U2") (pin "A12") (pinfunction "NC_4_A12") (pintype "passive+no_connect"))
    )
    (net (code "80") (name "unconnected-(U2B-NC_5-PadB1)") (class "Default")
      (node (ref "U2") (pin "B1") (pinfunction "NC_5_B1") (pintype "passive+no_connect"))
    )
    (net (code "81") (name "unconnected-(U2B-NC_6-PadB12)") (class "Default")
      (node (ref "U2") (pin "B12") (pinfunction "NC_6_B12") (pintype "passive+no_connect"))
    )
    (net (code "82") (name "unconnected-(U2B-NC_7-PadG11)") (class "Default")
      (node (ref "U2") (pin "G11") (pinfunction "NC_7_G11") (pintype "passive+no_connect"))
    )
    (net (code "83") (name "unconnected-(U2B-NC_8-PadK5)") (class "Default")
      (node (ref "U2") (pin "K5") (pinfunction "NC_8_K5") (pintype "passive+no_connect"))
    )
    (net (code "84") (name "unconnected-(U2B-NC_9-PadK8)") (class "Default")
      (node (ref "U2") (pin "K8") (pinfunction "NC_9_K8") (pintype "passive+no_connect"))
    )
    (net (code "85") (name "unconnected-(U2B-NC_10-PadN5)") (class "Default")
      (node (ref "U2") (pin "N5") (pinfunction "NC_10_N5") (pintype "passive+no_connect"))
    )
    (net (code "86") (name "unconnected-(U2B-NC_11-PadN8)") (class "Default")
      (node (ref "U2") (pin "N8") (pinfunction "NC_11_N8") (pintype "passive+no_connect"))
    )
    (net (code "87") (name "unconnected-(U2B-NC_12-PadAA1)") (class "Default")
      (node (ref "U2") (pin "AA1") (pinfunction "NC_12_AA1") (pintype "passive+no_connect"))
    )
    (net (code "88") (name "unconnected-(U2B-NC_13-PadAA12)") (class "Default")
      (node (ref "U2") (pin "AA12") (pinfunction "NC_13_AA12") (pintype "passive+no_connect"))
    )
    (net (code "89") (name "unconnected-(U2B-NC_14-PadAB1)") (class "Default")
      (node (ref "U2") (pin "AB1") (pinfunction "NC_14_AB1") (pintype "passive+no_connect"))
    )
    (net (code "90") (name "unconnected-(U2B-NC_15-PadAB2)") (class "Default")
      (node (ref "U2") (pin "AB2") (pinfunction "NC_15_AB2") (pintype "passive+no_connect"))
    )
    (net (code "91") (name "unconnected-(U2B-NC_16-PadAB11)") (class "Default")
      (node (ref "U2") (pin "AB11") (pinfunction "NC_16_AB11") (pintype "passive+no_connect"))
    )
    (net (code "92") (name "unconnected-(U2B-NC_17-PadAB12)") (class "Default")
      (node (ref "U2") (pin "AB12") (pinfunction "NC_17_AB12") (pintype "passive+no_connect"))
    )
  )
)
